# 7segement2digits1badidea-mk-3.net
KiCad netlist of a schematic drawn in EAGLE
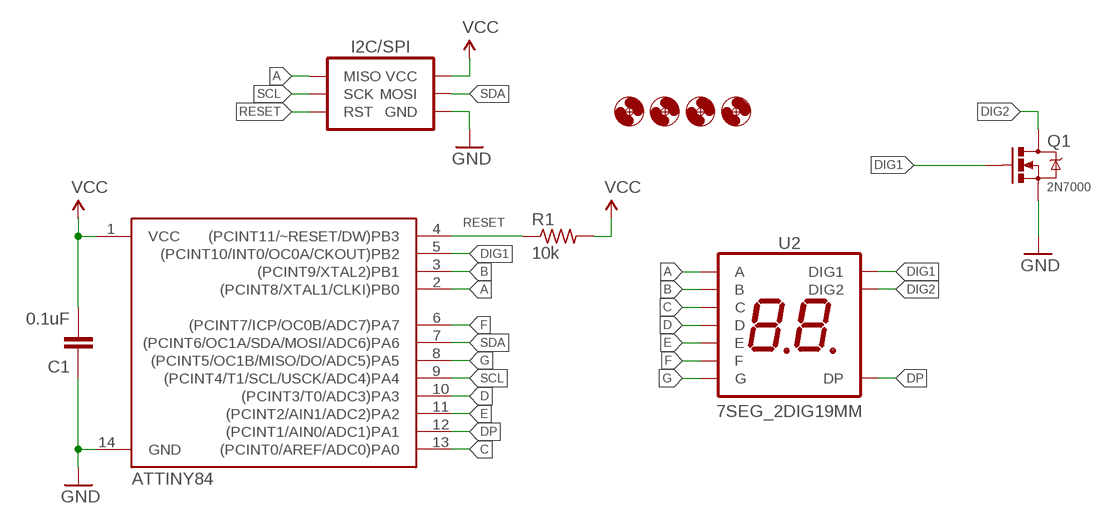
[diagram p0: schematic, sheet 1]

(export (version "E")
  (design (tool "Eeschema 10.0.6"))
  (components
    (comp (ref "C1")
      (value "0.1uF")
      (footprint "eagle-import:C025-024X044")
      (libsource (lib "eagle-import") (part "CAPACITOR-CERAMIC025-024X044"))
    )
    (comp (ref "H1")
      (value "HOLE#2")
      (footprint "eagle-import:HOLE-#2")
      (libsource (lib "eagle-import") (part "HOLE#2"))
    )
    (comp (ref "H2")
      (value "HOLE#2")
      (footprint "eagle-import:HOLE-#2")
      (libsource (lib "eagle-import") (part "HOLE#2"))
    )
    (comp (ref "H3")
      (value "HOLE#2")
      (footprint "eagle-import:HOLE-#2")
      (libsource (lib "eagle-import") (part "HOLE#2"))
    )
    (comp (ref "H4")
      (value "HOLE#2")
      (footprint "eagle-import:HOLE-#2")
      (libsource (lib "eagle-import") (part "HOLE#2"))
    )
    (comp (ref "I2C/SPI")
      (value "AVR_SPI_PRG_6PTH_INLINE_I2C")
      (footprint "eagle-import:AVR_ISP_INLINE_PTH_I2C")
      (libsource (lib "eagle-import") (part "AVR_SPI_PRG_6PTH_INLINE_I2C"))
    )
    (comp (ref "Q1")
      (value "2N7000")
      (footprint "eagle-import:TO-92-AMMO")
      (libsource (lib "eagle-import") (part "MOSFET-NCHANNEL2N7000-AMMO"))
    )
    (comp (ref "R1")
      (value "10k")
      (footprint "eagle-import:RESISTOR-AXIAL-PTH-7.68MM")
      (libsource (lib "eagle-import") (part "RESISTORPTH-AXIAL-7.68MM"))
    )
    (comp (ref "U1")
      (value "ATTINY84")
      (footprint "eagle-import:DIL14")
      (libsource (lib "eagle-import") (part "ATTINY84ATTINY84-20PU"))
    )
    (comp (ref "U2")
      (value "7SEG_2DIG19MM")
      (footprint "eagle-import:7SEG_2DIG_19MM")
      (libsource (lib "eagle-import") (part "7SEG_2DIG19MM"))
    )
  )
  (nets
    (net (code "1") (name "A") (class "Default")
      (node (ref "I2C/SPI") (pin "MISO") (pinfunction "MISO_MISO") (pintype "passive"))
      (node (ref "U1") (pin "2") (pinfunction "(PCINT8/XTAL1/CLKI)PB0_2") (pintype "bidirectional"))
      (node (ref "U2") (pin "10") (pinfunction "A_10") (pintype "passive"))
    )
    (net (code "2") (name "B") (class "Default")
      (node (ref "U1") (pin "3") (pinfunction "(PCINT9/XTAL2)PB1_3") (pintype "bidirectional"))
      (node (ref "U2") (pin "9") (pinfunction "B_9") (pintype "passive"))
    )
    (net (code "3") (name "C") (class "Default")
      (node (ref "U1") (pin "13") (pinfunction "(PCINT0/AREF/ADC0)PA0_13") (pintype "bidirectional"))
      (node (ref "U2") (pin "1") (pinfunction "C_1") (pintype "passive"))
    )
    (net (code "4") (name "D") (class "Default")
      (node (ref "U1") (pin "10") (pinfunction "(PCINT3/T0/ADC3)PA3_10") (pintype "bidirectional"))
      (node (ref "U2") (pin "4") (pinfunction "D_4") (pintype "passive"))
    )
    (net (code "5") (name "DIG1") (class "Default")
      (node (ref "Q1") (pin "2") (pinfunction "G_2") (pintype "passive"))
      (node (ref "U1") (pin "5") (pinfunction "(PCINT10/INT0/OC0A/CKOUT)PB2_5") (pintype "bidirectional"))
      (node (ref "U2") (pin "8") (pinfunction "DIG1_8") (pintype "passive"))
    )
    (net (code "6") (name "DIG2") (class "Default")
      (node (ref "Q1") (pin "3") (pinfunction "D_3") (pintype "passive"))
      (node (ref "U2") (pin "7") (pinfunction "DIG2_7") (pintype "passive"))
    )
    (net (code "7") (name "DP") (class "Default")
      (node (ref "U1") (pin "12") (pinfunction "(PCINT1/AIN0/ADC1)PA1_12") (pintype "bidirectional"))
      (node (ref "U2") (pin "2") (pinfunction "DP_2") (pintype "passive"))
    )
    (net (code "8") (name "E") (class "Default")
      (node (ref "U1") (pin "11") (pinfunction "(PCINT2/AIN1/ADC2)PA2_11") (pintype "bidirectional"))
      (node (ref "U2") (pin "3") (pinfunction "E_3") (pintype "passive"))
    )
    (net (code "9") (name "F") (class "Default")
      (node (ref "U1") (pin "6") (pinfunction "(PCINT7/ICP/OC0B/ADC7)PA7_6") (pintype "bidirectional"))
      (node (ref "U2") (pin "6") (pinfunction "F_6") (pintype "passive"))
    )
    (net (code "10") (name "G") (class "Default")
      (node (ref "U1") (pin "8") (pinfunction "(PCINT5/OC1B/MISO/DO/ADC5)PA5_8") (pintype "bidirectional"))
      (node (ref "U2") (pin "5") (pinfunction "G_5") (pintype "passive"))
    )
    (net (code "11") (name "GND") (class "Default")
      (node (ref "C1") (pin "1") (pinfunction "1_1") (pintype "passive"))
      (node (ref "I2C/SPI") (pin "GND") (pinfunction "GND_GND") (pintype "passive"))
      (node (ref "Q1") (pin "1") (pinfunction "S_1") (pintype "passive"))
      (node (ref "U1") (pin "14") (pinfunction "GND_14") (pintype "bidirectional"))
    )
    (net (code "12") (name "RESET") (class "Default")
      (node (ref "I2C/SPI") (pin "RESET") (pinfunction "RST_RESET") (pintype "passive"))
      (node (ref "R1") (pin "P$1") (pinfunction "1_P$1") (pintype "passive"))
      (node (ref "U1") (pin "4") (pinfunction "(PCINT11/~{RESET/DW})PB3_4") (pintype "bidirectional"))
    )
    (net (code "13") (name "SCL") (class "Default")
      (node (ref "I2C/SPI") (pin "SCK") (pinfunction "SCK_SCK") (pintype "passive"))
      (node (ref "U1") (pin "9") (pinfunction "(PCINT4/T1/SCL/USCK/ADC4)PA4_9") (pintype "bidirectional"))
    )
    (net (code "14") (name "SDA") (class "Default")
      (node (ref "I2C/SPI") (pin "MOSI") (pinfunction "MOSI_MOSI") (pintype "passive"))
      (node (ref "U1") (pin "7") (pinfunction "(PCINT6/OC1A/SDA/MOSI/ADC6)PA6_7") (pintype "bidirectional"))
    )
    (net (code "15") (name "VCC") (class "Default")
      (node (ref "C1") (pin "2") (pinfunction "2_2") (pintype "passive"))
      (node (ref "I2C/SPI") (pin "VCC") (pinfunction "VCC_VCC") (pintype "passive"))
      (node (ref "R1") (pin "P$2") (pinfunction "2_P$2") (pintype "passive"))
      (node (ref "U1") (pin "1") (pinfunction "VCC_1") (pintype "bidirectional"))
    )
  )
)
